# rk86-kbd.net
KiCad netlist of a schematic drawn in EAGLE
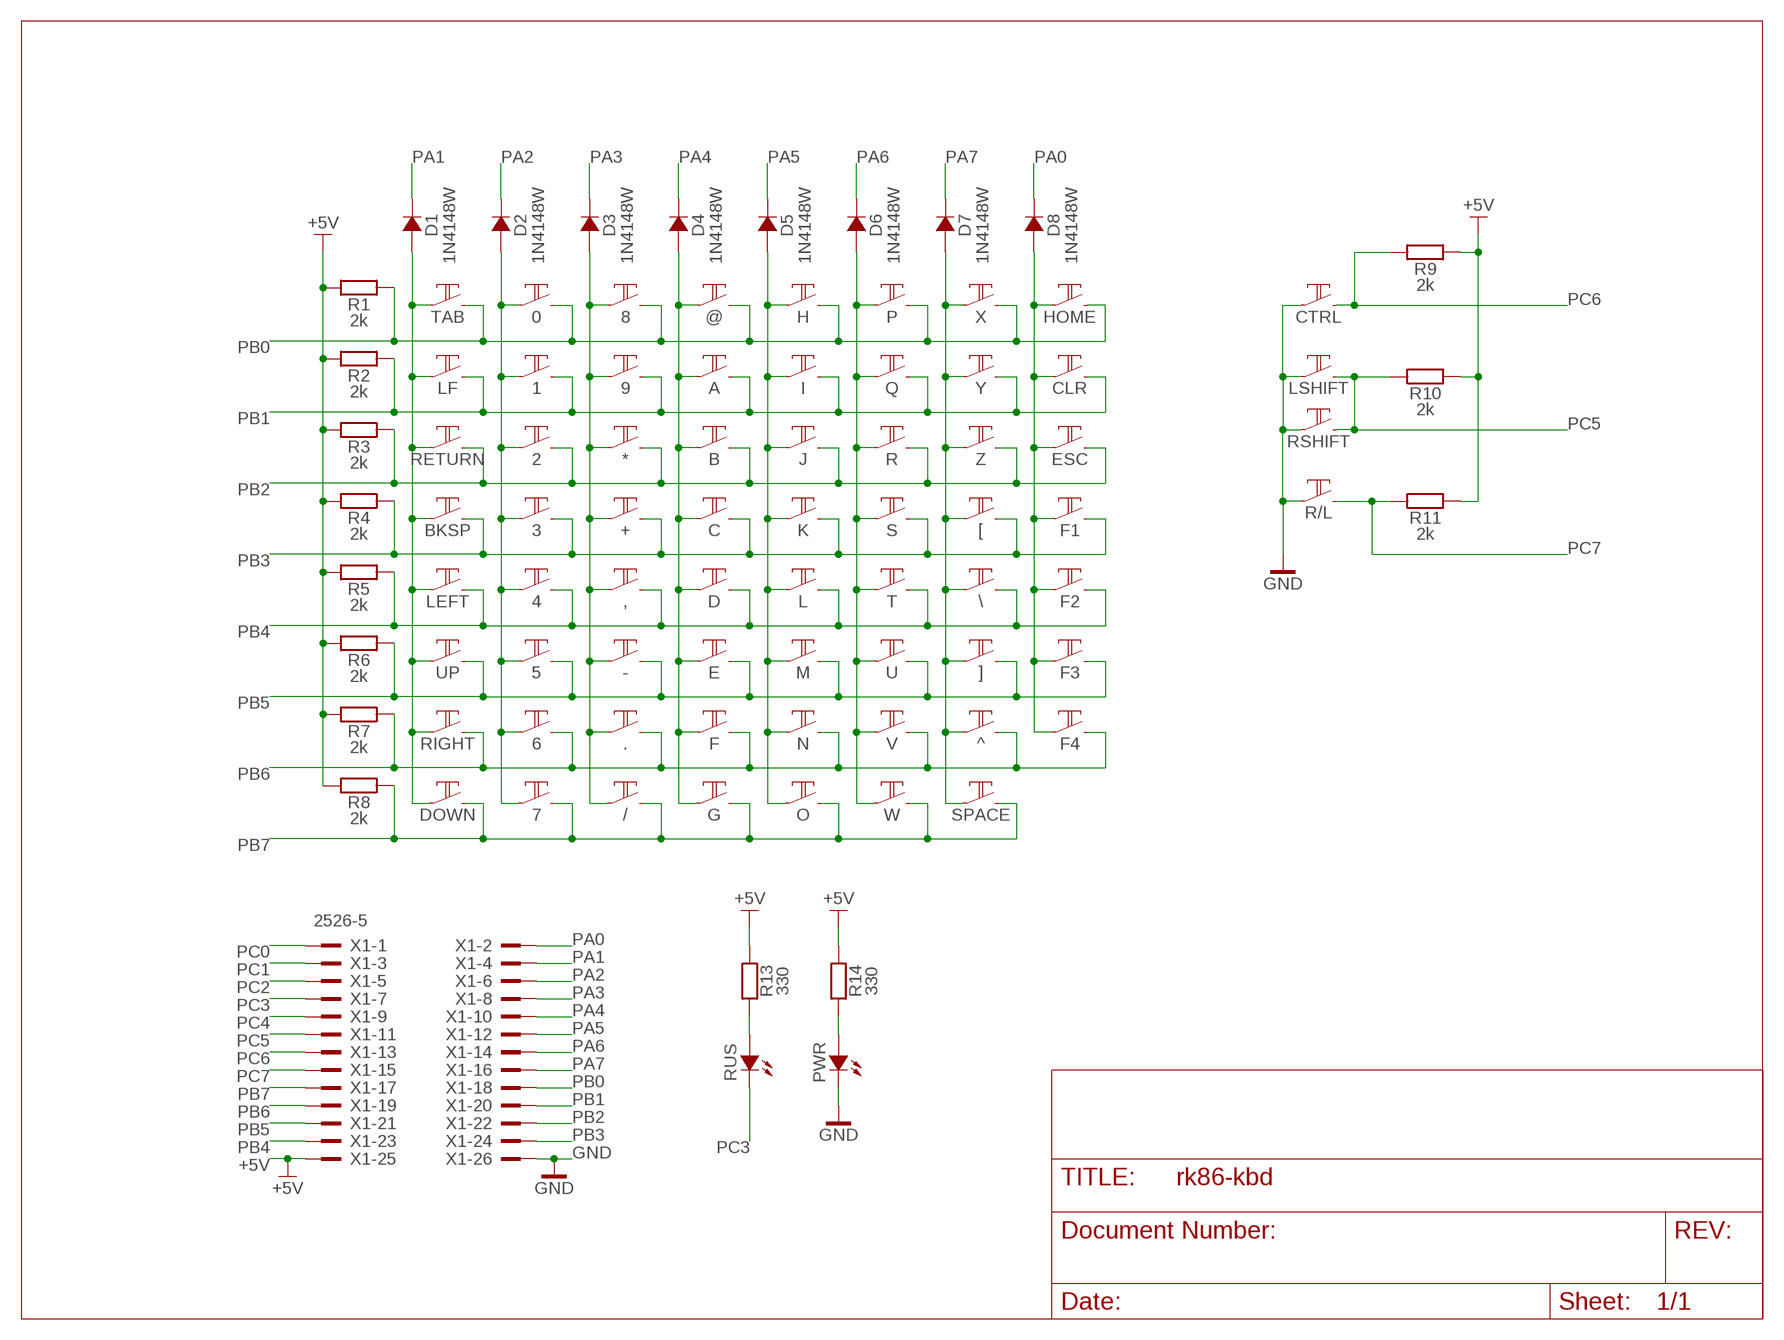
[diagram p0: schematic, sheet 1]

(export (version "E")
  (design (tool "Eeschema 10.0.6"))
  (components
    (comp (ref "*")
      (value "TACT6S-15")
      (footprint "eagle-import:TACT_6X6_SMT_15")
      (libsource (lib "eagle-import") (part "TACT6S-15"))
    )
    (comp (ref "+")
      (value "TACT6S-15")
      (footprint "eagle-import:TACT_6X6_SMT_15")
      (libsource (lib "eagle-import") (part "TACT6S-15"))
    )
    (comp (ref ",")
      (value "TACT6S-15")
      (footprint "eagle-import:TACT_6X6_SMT_15")
      (libsource (lib "eagle-import") (part "TACT6S-15"))
    )
    (comp (ref "-")
      (value "TACT6S-15")
      (footprint "eagle-import:TACT_6X6_SMT_15")
      (libsource (lib "eagle-import") (part "TACT6S-15"))
    )
    (comp (ref ".")
      (value "TACT6S-15")
      (footprint "eagle-import:TACT_6X6_SMT_15")
      (libsource (lib "eagle-import") (part "TACT6S-15"))
    )
    (comp (ref "/")
      (value "TACT6S-15")
      (footprint "eagle-import:TACT_6X6_SMT_15")
      (libsource (lib "eagle-import") (part "TACT6S-15"))
    )
    (comp (ref "0")
      (value "TACT6S-15")
      (footprint "eagle-import:TACT_6X6_SMT_15")
      (libsource (lib "eagle-import") (part "TACT6S-15"))
    )
    (comp (ref "1")
      (value "TACT6S-15")
      (footprint "eagle-import:TACT_6X6_SMT_15")
      (libsource (lib "eagle-import") (part "TACT6S-15"))
    )
    (comp (ref "2")
      (value "TACT6S-15")
      (footprint "eagle-import:TACT_6X6_SMT_15")
      (libsource (lib "eagle-import") (part "TACT6S-15"))
    )
    (comp (ref "3")
      (value "TACT6S-15")
      (footprint "eagle-import:TACT_6X6_SMT_15")
      (libsource (lib "eagle-import") (part "TACT6S-15"))
    )
    (comp (ref "4")
      (value "TACT6S-15")
      (footprint "eagle-import:TACT_6X6_SMT_15")
      (libsource (lib "eagle-import") (part "TACT6S-15"))
    )
    (comp (ref "5")
      (value "TACT6S-15")
      (footprint "eagle-import:TACT_6X6_SMT_15")
      (libsource (lib "eagle-import") (part "TACT6S-15"))
    )
    (comp (ref "6")
      (value "TACT6S-15")
      (footprint "eagle-import:TACT_6X6_SMT_15")
      (libsource (lib "eagle-import") (part "TACT6S-15"))
    )
    (comp (ref "7")
      (value "TACT6S-15")
      (footprint "eagle-import:TACT_6X6_SMT_15")
      (libsource (lib "eagle-import") (part "TACT6S-15"))
    )
    (comp (ref "8")
      (value "TACT6S-15")
      (footprint "eagle-import:TACT_6X6_SMT_15")
      (libsource (lib "eagle-import") (part "TACT6S-15"))
    )
    (comp (ref "9")
      (value "TACT6S-15")
      (footprint "eagle-import:TACT_6X6_SMT_15")
      (libsource (lib "eagle-import") (part "TACT6S-15"))
    )
    (comp (ref "@")
      (value "TACT6S-15")
      (footprint "eagle-import:TACT_6X6_SMT_15")
      (libsource (lib "eagle-import") (part "TACT6S-15"))
    )
    (comp (ref "A")
      (value "TACT6S-15")
      (footprint "eagle-import:TACT_6X6_SMT_15")
      (libsource (lib "eagle-import") (part "TACT6S-15"))
    )
    (comp (ref "B")
      (value "TACT6S-15")
      (footprint "eagle-import:TACT_6X6_SMT_15")
      (libsource (lib "eagle-import") (part "TACT6S-15"))
    )
    (comp (ref "BKSP")
      (value "TACT6S-15")
      (footprint "eagle-import:TACT_6X6_SMT_15")
      (libsource (lib "eagle-import") (part "TACT6S-15"))
    )
    (comp (ref "C")
      (value "TACT6S-15")
      (footprint "eagle-import:TACT_6X6_SMT_15")
      (libsource (lib "eagle-import") (part "TACT6S-15"))
    )
    (comp (ref "CLR")
      (value "TACT6S-15")
      (footprint "eagle-import:TACT_6X6_SMT_15")
      (libsource (lib "eagle-import") (part "TACT6S-15"))
    )
    (comp (ref "CTRL")
      (value "TACT6S-15")
      (footprint "eagle-import:TACT_6X6_SMT_15")
      (libsource (lib "eagle-import") (part "TACT6S-15"))
    )
    (comp (ref "D")
      (value "TACT6S-15")
      (footprint "eagle-import:TACT_6X6_SMT_15")
      (libsource (lib "eagle-import") (part "TACT6S-15"))
    )
    (comp (ref "D1")
      (value "1N4148W")
      (footprint "eagle-import:SOD123")
      (libsource (lib "eagle-import") (part "1N4148W"))
    )
    (comp (ref "D2")
      (value "1N4148W")
      (footprint "eagle-import:SOD123")
      (libsource (lib "eagle-import") (part "1N4148W"))
    )
    (comp (ref "D3")
      (value "1N4148W")
      (footprint "eagle-import:SOD123")
      (libsource (lib "eagle-import") (part "1N4148W"))
    )
    (comp (ref "D4")
      (value "1N4148W")
      (footprint "eagle-import:SOD123")
      (libsource (lib "eagle-import") (part "1N4148W"))
    )
    (comp (ref "D5")
      (value "1N4148W")
      (footprint "eagle-import:SOD123")
      (libsource (lib "eagle-import") (part "1N4148W"))
    )
    (comp (ref "D6")
      (value "1N4148W")
      (footprint "eagle-import:SOD123")
      (libsource (lib "eagle-import") (part "1N4148W"))
    )
    (comp (ref "D7")
      (value "1N4148W")
      (footprint "eagle-import:SOD123")
      (libsource (lib "eagle-import") (part "1N4148W"))
    )
    (comp (ref "D8")
      (value "1N4148W")
      (footprint "eagle-import:SOD123")
      (libsource (lib "eagle-import") (part "1N4148W"))
    )
    (comp (ref "DOWN")
      (value "TACT6S-15")
      (footprint "eagle-import:TACT_6X6_SMT_15")
      (libsource (lib "eagle-import") (part "TACT6S-15"))
    )
    (comp (ref "E")
      (value "TACT6S-15")
      (footprint "eagle-import:TACT_6X6_SMT_15")
      (libsource (lib "eagle-import") (part "TACT6S-15"))
    )
    (comp (ref "ESC")
      (value "TACT6S-15")
      (footprint "eagle-import:TACT_6X6_SMT_15")
      (libsource (lib "eagle-import") (part "TACT6S-15"))
    )
    (comp (ref "F")
      (value "TACT6S-15")
      (footprint "eagle-import:TACT_6X6_SMT_15")
      (libsource (lib "eagle-import") (part "TACT6S-15"))
    )
    (comp (ref "F1")
      (value "TACT6S-15")
      (footprint "eagle-import:TACT_6X6_SMT_15")
      (libsource (lib "eagle-import") (part "TACT6S-15"))
    )
    (comp (ref "F2")
      (value "TACT6S-15")
      (footprint "eagle-import:TACT_6X6_SMT_15")
      (libsource (lib "eagle-import") (part "TACT6S-15"))
    )
    (comp (ref "F3")
      (value "TACT6S-15")
      (footprint "eagle-import:TACT_6X6_SMT_15")
      (libsource (lib "eagle-import") (part "TACT6S-15"))
    )
    (comp (ref "F4")
      (value "TACT6S-15")
      (footprint "eagle-import:TACT_6X6_SMT_15")
      (libsource (lib "eagle-import") (part "TACT6S-15"))
    )
    (comp (ref "G")
      (value "TACT6S-15")
      (footprint "eagle-import:TACT_6X6_SMT_15")
      (libsource (lib "eagle-import") (part "TACT6S-15"))
    )
    (comp (ref "H")
      (value "TACT6S-15")
      (footprint "eagle-import:TACT_6X6_SMT_15")
      (libsource (lib "eagle-import") (part "TACT6S-15"))
    )
    (comp (ref "HOME")
      (value "TACT6S-15")
      (footprint "eagle-import:TACT_6X6_SMT_15")
      (libsource (lib "eagle-import") (part "TACT6S-15"))
    )
    (comp (ref "I")
      (value "TACT6S-15")
      (footprint "eagle-import:TACT_6X6_SMT_15")
      (libsource (lib "eagle-import") (part "TACT6S-15"))
    )
    (comp (ref "J")
      (value "TACT6S-15")
      (footprint "eagle-import:TACT_6X6_SMT_15")
      (libsource (lib "eagle-import") (part "TACT6S-15"))
    )
    (comp (ref "K")
      (value "TACT6S-15")
      (footprint "eagle-import:TACT_6X6_SMT_15")
      (libsource (lib "eagle-import") (part "TACT6S-15"))
    )
    (comp (ref "L")
      (value "TACT6S-15")
      (footprint "eagle-import:TACT_6X6_SMT_15")
      (libsource (lib "eagle-import") (part "TACT6S-15"))
    )
    (comp (ref "LEFT")
      (value "TACT6S-15")
      (footprint "eagle-import:TACT_6X6_SMT_15")
      (libsource (lib "eagle-import") (part "TACT6S-15"))
    )
    (comp (ref "LF")
      (value "TACT6S-15")
      (footprint "eagle-import:TACT_6X6_SMT_15")
      (libsource (lib "eagle-import") (part "TACT6S-15"))
    )
    (comp (ref "LSHIFT")
      (value "TACT6S-15")
      (footprint "eagle-import:TACT_6X6_SMT_15")
      (libsource (lib "eagle-import") (part "TACT6S-15"))
    )
    (comp (ref "M")
      (value "TACT6S-15")
      (footprint "eagle-import:TACT_6X6_SMT_15")
      (libsource (lib "eagle-import") (part "TACT6S-15"))
    )
    (comp (ref "N")
      (value "TACT6S-15")
      (footprint "eagle-import:TACT_6X6_SMT_15")
      (libsource (lib "eagle-import") (part "TACT6S-15"))
    )
    (comp (ref "O")
      (value "TACT6S-15")
      (footprint "eagle-import:TACT_6X6_SMT_15")
      (libsource (lib "eagle-import") (part "TACT6S-15"))
    )
    (comp (ref "P")
      (value "TACT6S-15")
      (footprint "eagle-import:TACT_6X6_SMT_15")
      (libsource (lib "eagle-import") (part "TACT6S-15"))
    )
    (comp (ref "PWR")
      (value "LED0805")
      (footprint "eagle-import:0805POL")
      (libsource (lib "eagle-import") (part "LED0805"))
    )
    (comp (ref "Q")
      (value "TACT6S-15")
      (footprint "eagle-import:TACT_6X6_SMT_15")
      (libsource (lib "eagle-import") (part "TACT6S-15"))
    )
    (comp (ref "R")
      (value "TACT6S-15")
      (footprint "eagle-import:TACT_6X6_SMT_15")
      (libsource (lib "eagle-import") (part "TACT6S-15"))
    )
    (comp (ref "R/L")
      (value "TACT6S-15")
      (footprint "eagle-import:TACT_6X6_SMT_15")
      (libsource (lib "eagle-import") (part "TACT6S-15"))
    )
    (comp (ref "R1")
      (value "2k")
      (footprint "eagle-import:0805")
      (libsource (lib "eagle-import") (part "RESISTOR0805"))
    )
    (comp (ref "R2")
      (value "2k")
      (footprint "eagle-import:0805")
      (libsource (lib "eagle-import") (part "RESISTOR0805"))
    )
    (comp (ref "R3")
      (value "2k")
      (footprint "eagle-import:0805")
      (libsource (lib "eagle-import") (part "RESISTOR0805"))
    )
    (comp (ref "R4")
      (value "2k")
      (footprint "eagle-import:0805")
      (libsource (lib "eagle-import") (part "RESISTOR0805"))
    )
    (comp (ref "R5")
      (value "2k")
      (footprint "eagle-import:0805")
      (libsource (lib "eagle-import") (part "RESISTOR0805"))
    )
    (comp (ref "R6")
      (value "2k")
      (footprint "eagle-import:0805")
      (libsource (lib "eagle-import") (part "RESISTOR0805"))
    )
    (comp (ref "R7")
      (value "2k")
      (footprint "eagle-import:0805")
      (libsource (lib "eagle-import") (part "RESISTOR0805"))
    )
    (comp (ref "R8")
      (value "2k")
      (footprint "eagle-import:0805")
      (libsource (lib "eagle-import") (part "RESISTOR0805"))
    )
    (comp (ref "R9")
      (value "2k")
      (footprint "eagle-import:0805")
      (libsource (lib "eagle-import") (part "RESISTOR0805"))
    )
    (comp (ref "R10")
      (value "2k")
      (footprint "eagle-import:0805")
      (libsource (lib "eagle-import") (part "RESISTOR0805"))
    )
    (comp (ref "R11")
      (value "2k")
      (footprint "eagle-import:0805")
      (libsource (lib "eagle-import") (part "RESISTOR0805"))
    )
    (comp (ref "R13")
      (value "330")
      (footprint "eagle-import:0805")
      (libsource (lib "eagle-import") (part "RESISTOR0805"))
    )
    (comp (ref "R14")
      (value "330")
      (footprint "eagle-import:0805")
      (libsource (lib "eagle-import") (part "RESISTOR0805"))
    )
    (comp (ref "RETURN")
      (value "TACT6S-15")
      (footprint "eagle-import:TACT_6X6_SMT_15")
      (libsource (lib "eagle-import") (part "TACT6S-15"))
    )
    (comp (ref "RIGHT")
      (value "TACT6S-15")
      (footprint "eagle-import:TACT_6X6_SMT_15")
      (libsource (lib "eagle-import") (part "TACT6S-15"))
    )
    (comp (ref "RSHIFT")
      (value "TACT6S-15")
      (footprint "eagle-import:TACT_6X6_SMT_15")
      (libsource (lib "eagle-import") (part "TACT6S-15"))
    )
    (comp (ref "RUS")
      (value "LED0805")
      (footprint "eagle-import:0805POL")
      (libsource (lib "eagle-import") (part "LED0805"))
    )
    (comp (ref "S")
      (value "TACT6S-15")
      (footprint "eagle-import:TACT_6X6_SMT_15")
      (libsource (lib "eagle-import") (part "TACT6S-15"))
    )
    (comp (ref "SPACE")
      (value "TACT6S-15")
      (footprint "eagle-import:TACT_6X6_SMT_15")
      (libsource (lib "eagle-import") (part "TACT6S-15"))
    )
    (comp (ref "T")
      (value "TACT6S-15")
      (footprint "eagle-import:TACT_6X6_SMT_15")
      (libsource (lib "eagle-import") (part "TACT6S-15"))
    )
    (comp (ref "TAB")
      (value "TACT6S-15")
      (footprint "eagle-import:TACT_6X6_SMT_15")
      (libsource (lib "eagle-import") (part "TACT6S-15"))
    )
    (comp (ref "U")
      (value "TACT6S-15")
      (footprint "eagle-import:TACT_6X6_SMT_15")
      (libsource (lib "eagle-import") (part "TACT6S-15"))
    )
    (comp (ref "UP")
      (value "TACT6S-15")
      (footprint "eagle-import:TACT_6X6_SMT_15")
      (libsource (lib "eagle-import") (part "TACT6S-15"))
    )
    (comp (ref "V")
      (value "TACT6S-15")
      (footprint "eagle-import:TACT_6X6_SMT_15")
      (libsource (lib "eagle-import") (part "TACT6S-15"))
    )
    (comp (ref "W")
      (value "TACT6S-15")
      (footprint "eagle-import:TACT_6X6_SMT_15")
      (libsource (lib "eagle-import") (part "TACT6S-15"))
    )
    (comp (ref "X")
      (value "TACT6S-15")
      (footprint "eagle-import:TACT_6X6_SMT_15")
      (libsource (lib "eagle-import") (part "TACT6S-15"))
    )
    (comp (ref "X1")
      (value "2526-5")
      (footprint "eagle-import:PAK100_2500-5-26")
      (libsource (lib "eagle-import") (part "2526-5"))
    )
    (comp (ref "Y")
      (value "TACT6S-15")
      (footprint "eagle-import:TACT_6X6_SMT_15")
      (libsource (lib "eagle-import") (part "TACT6S-15"))
    )
    (comp (ref "Z")
      (value "TACT6S-15")
      (footprint "eagle-import:TACT_6X6_SMT_15")
      (libsource (lib "eagle-import") (part "TACT6S-15"))
    )
    (comp (ref "[")
      (value "TACT6S-15")
      (footprint "eagle-import:TACT_6X6_SMT_15")
      (libsource (lib "eagle-import") (part "TACT6S-15"))
    )
    (comp (ref "\\\\")
      (value "TACT6S-15")
      (footprint "eagle-import:TACT_6X6_SMT_15")
      (libsource (lib "eagle-import") (part "TACT6S-15"))
    )
    (comp (ref "]")
      (value "TACT6S-15")
      (footprint "eagle-import:TACT_6X6_SMT_15")
      (libsource (lib "eagle-import") (part "TACT6S-15"))
    )
    (comp (ref "^")
      (value "TACT6S-15")
      (footprint "eagle-import:TACT_6X6_SMT_15")
      (libsource (lib "eagle-import") (part "TACT6S-15"))
    )
  )
  (nets
    (net (code "1") (name "+5V") (class "Default")
      (node (ref "R1") (pin "1") (pinfunction "P$1_1") (pintype "passive"))
      (node (ref "R10") (pin "2") (pinfunction "P$2_2") (pintype "passive"))
      (node (ref "R11") (pin "2") (pinfunction "P$2_2") (pintype "passive"))
      (node (ref "R13") (pin "2") (pinfunction "P$2_2") (pintype "passive"))
      (node (ref "R14") (pin "2") (pinfunction "P$2_2") (pintype "passive"))
      (node (ref "R2") (pin "1") (pinfunction "P$1_1") (pintype "passive"))
      (node (ref "R3") (pin "1") (pinfunction "P$1_1") (pintype "passive"))
      (node (ref "R4") (pin "1") (pinfunction "P$1_1") (pintype "passive"))
      (node (ref "R5") (pin "1") (pinfunction "P$1_1") (pintype "passive"))
      (node (ref "R6") (pin "1") (pinfunction "P$1_1") (pintype "passive"))
      (node (ref "R7") (pin "1") (pinfunction "P$1_1") (pintype "passive"))
      (node (ref "R8") (pin "1") (pinfunction "P$1_1") (pintype "passive"))
      (node (ref "R9") (pin "2") (pinfunction "P$2_2") (pintype "passive"))
      (node (ref "X1") (pin "25") (pinfunction "KL_25") (pintype "passive"))
    )
    (net (code "2") (name "/PA0") (class "Default")
      (node (ref "D8") (pin "K") (pinfunction "K_K") (pintype "passive"))
      (node (ref "X1") (pin "2") (pinfunction "KL_2") (pintype "passive"))
    )
    (net (code "3") (name "/PA1") (class "Default")
      (node (ref "D1") (pin "K") (pinfunction "K_K") (pintype "passive"))
      (node (ref "X1") (pin "4") (pinfunction "KL_4") (pintype "passive"))
    )
    (net (code "4") (name "/PA2") (class "Default")
      (node (ref "D2") (pin "K") (pinfunction "K_K") (pintype "passive"))
      (node (ref "X1") (pin "6") (pinfunction "KL_6") (pintype "passive"))
    )
    (net (code "5") (name "/PA3") (class "Default")
      (node (ref "D3") (pin "K") (pinfunction "K_K") (pintype "passive"))
      (node (ref "X1") (pin "8") (pinfunction "KL_8") (pintype "passive"))
    )
    (net (code "6") (name "/PA4") (class "Default")
      (node (ref "D4") (pin "K") (pinfunction "K_K") (pintype "passive"))
      (node (ref "X1") (pin "10") (pinfunction "KL_10") (pintype "passive"))
    )
    (net (code "7") (name "/PA5") (class "Default")
      (node (ref "D5") (pin "K") (pinfunction "K_K") (pintype "passive"))
      (node (ref "X1") (pin "12") (pinfunction "KL_12") (pintype "passive"))
    )
    (net (code "8") (name "/PA6") (class "Default")
      (node (ref "D6") (pin "K") (pinfunction "K_K") (pintype "passive"))
      (node (ref "X1") (pin "14") (pinfunction "KL_14") (pintype "passive"))
    )
    (net (code "9") (name "/PA7") (class "Default")
      (node (ref "D7") (pin "K") (pinfunction "K_K") (pintype "passive"))
      (node (ref "X1") (pin "16") (pinfunction "KL_16") (pintype "passive"))
    )
    (net (code "10") (name "/PB0") (class "Default")
      (node (ref "0") (pin "3") (pinfunction "NO_3") (pintype "passive"))
      (node (ref "0") (pin "4") (pinfunction "NO_4") (pintype "passive"))
      (node (ref "8") (pin "3") (pinfunction "NO_3") (pintype "passive"))
      (node (ref "8") (pin "4") (pinfunction "NO_4") (pintype "passive"))
      (node (ref "@") (pin "3") (pinfunction "NO_3") (pintype "passive"))
      (node (ref "@") (pin "4") (pinfunction "NO_4") (pintype "passive"))
      (node (ref "H") (pin "3") (pinfunction "NO_3") (pintype "passive"))
      (node (ref "H") (pin "4") (pinfunction "NO_4") (pintype "passive"))
      (node (ref "HOME") (pin "3") (pinfunction "NO_3") (pintype "passive"))
      (node (ref "HOME") (pin "4") (pinfunction "NO_4") (pintype "passive"))
      (node (ref "P") (pin "3") (pinfunction "NO_3") (pintype "passive"))
      (node (ref "P") (pin "4") (pinfunction "NO_4") (pintype "passive"))
      (node (ref "R1") (pin "2") (pinfunction "P$2_2") (pintype "passive"))
      (node (ref "TAB") (pin "3") (pinfunction "NO_3") (pintype "passive"))
      (node (ref "TAB") (pin "4") (pinfunction "NO_4") (pintype "passive"))
      (node (ref "X") (pin "3") (pinfunction "NO_3") (pintype "passive"))
      (node (ref "X") (pin "4") (pinfunction "NO_4") (pintype "passive"))
      (node (ref "X1") (pin "18") (pinfunction "KL_18") (pintype "passive"))
    )
    (net (code "11") (name "/PB1") (class "Default")
      (node (ref "1") (pin "3") (pinfunction "NO_3") (pintype "passive"))
      (node (ref "1") (pin "4") (pinfunction "NO_4") (pintype "passive"))
      (node (ref "9") (pin "3") (pinfunction "NO_3") (pintype "passive"))
      (node (ref "9") (pin "4") (pinfunction "NO_4") (pintype "passive"))
      (node (ref "A") (pin "3") (pinfunction "NO_3") (pintype "passive"))
      (node (ref "A") (pin "4") (pinfunction "NO_4") (pintype "passive"))
      (node (ref "CLR") (pin "3") (pinfunction "NO_3") (pintype "passive"))
      (node (ref "CLR") (pin "4") (pinfunction "NO_4") (pintype "passive"))
      (node (ref "I") (pin "3") (pinfunction "NO_3") (pintype "passive"))
      (node (ref "I") (pin "4") (pinfunction "NO_4") (pintype "passive"))
      (node (ref "LF") (pin "3") (pinfunction "NO_3") (pintype "passive"))
      (node (ref "LF") (pin "4") (pinfunction "NO_4") (pintype "passive"))
      (node (ref "Q") (pin "3") (pinfunction "NO_3") (pintype "passive"))
      (node (ref "Q") (pin "4") (pinfunction "NO_4") (pintype "passive"))
      (node (ref "R2") (pin "2") (pinfunction "P$2_2") (pintype "passive"))
      (node (ref "X1") (pin "20") (pinfunction "KL_20") (pintype "passive"))
      (node (ref "Y") (pin "3") (pinfunction "NO_3") (pintype "passive"))
      (node (ref "Y") (pin "4") (pinfunction "NO_4") (pintype "passive"))
    )
    (net (code "12") (name "/PB2") (class "Default")
      (node (ref "*") (pin "3") (pinfunction "NO_3") (pintype "passive"))
      (node (ref "*") (pin "4") (pinfunction "NO_4") (pintype "passive"))
      (node (ref "2") (pin "3") (pinfunction "NO_3") (pintype "passive"))
      (node (ref "2") (pin "4") (pinfunction "NO_4") (pintype "passive"))
      (node (ref "B") (pin "3") (pinfunction "NO_3") (pintype "passive"))
      (node (ref "B") (pin "4") (pinfunction "NO_4") (pintype "passive"))
      (node (ref "ESC") (pin "3") (pinfunction "NO_3") (pintype "passive"))
      (node (ref "ESC") (pin "4") (pinfunction "NO_4") (pintype "passive"))
      (node (ref "J") (pin "3") (pinfunction "NO_3") (pintype "passive"))
      (node (ref "J") (pin "4") (pinfunction "NO_4") (pintype "passive"))
      (node (ref "R") (pin "3") (pinfunction "NO_3") (pintype "passive"))
      (node (ref "R") (pin "4") (pinfunction "NO_4") (pintype "passive"))
      (node (ref "R3") (pin "2") (pinfunction "P$2_2") (pintype "passive"))
      (node (ref "RETURN") (pin "3") (pinfunction "NO_3") (pintype "passive"))
      (node (ref "RETURN") (pin "4") (pinfunction "NO_4") (pintype "passive"))
      (node (ref "X1") (pin "22") (pinfunction "KL_22") (pintype "passive"))
      (node (ref "Z") (pin "3") (pinfunction "NO_3") (pintype "passive"))
      (node (ref "Z") (pin "4") (pinfunction "NO_4") (pintype "passive"))
    )
    (net (code "13") (name "/PB3") (class "Default")
      (node (ref "+") (pin "3") (pinfunction "NO_3") (pintype "passive"))
      (node (ref "+") (pin "4") (pinfunction "NO_4") (pintype "passive"))
      (node (ref "3") (pin "3") (pinfunction "NO_3") (pintype "passive"))
      (node (ref "3") (pin "4") (pinfunction "NO_4") (pintype "passive"))
      (node (ref "BKSP") (pin "3") (pinfunction "NO_3") (pintype "passive"))
      (node (ref "BKSP") (pin "4") (pinfunction "NO_4") (pintype "passive"))
      (node (ref "C") (pin "3") (pinfunction "NO_3") (pintype "passive"))
      (node (ref "C") (pin "4") (pinfunction "NO_4") (pintype "passive"))
      (node (ref "F1") (pin "3") (pinfunction "NO_3") (pintype "passive"))
      (node (ref "F1") (pin "4") (pinfunction "NO_4") (pintype "passive"))
      (node (ref "K") (pin "3") (pinfunction "NO_3") (pintype "passive"))
      (node (ref "K") (pin "4") (pinfunction "NO_4") (pintype "passive"))
      (node (ref "R4") (pin "2") (pinfunction "P$2_2") (pintype "passive"))
      (node (ref "S") (pin "3") (pinfunction "NO_3") (pintype "passive"))
      (node (ref "S") (pin "4") (pinfunction "NO_4") (pintype "passive"))
      (node (ref "X1") (pin "24") (pinfunction "KL_24") (pintype "passive"))
      (node (ref "[") (pin "3") (pinfunction "NO_3") (pintype "passive"))
      (node (ref "[") (pin "4") (pinfunction "NO_4") (pintype "passive"))
    )
    (net (code "14") (name "/PB4") (class "Default")
      (node (ref ",") (pin "3") (pinfunction "NO_3") (pintype "passive"))
      (node (ref ",") (pin "4") (pinfunction "NO_4") (pintype "passive"))
      (node (ref "4") (pin "3") (pinfunction "NO_3") (pintype "passive"))
      (node (ref "4") (pin "4") (pinfunction "NO_4") (pintype "passive"))
      (node (ref "D") (pin "3") (pinfunction "NO_3") (pintype "passive"))
      (node (ref "D") (pin "4") (pinfunction "NO_4") (pintype "passive"))
      (node (ref "F2") (pin "3") (pinfunction "NO_3") (pintype "passive"))
      (node (ref "F2") (pin "4") (pinfunction "NO_4") (pintype "passive"))
      (node (ref "L") (pin "3") (pinfunction "NO_3") (pintype "passive"))
      (node (ref "L") (pin "4") (pinfunction "NO_4") (pintype "passive"))
      (node (ref "LEFT") (pin "3") (pinfunction "NO_3") (pintype "passive"))
      (node (ref "LEFT") (pin "4") (pinfunction "NO_4") (pintype "passive"))
      (node (ref "R5") (pin "2") (pinfunction "P$2_2") (pintype "passive"))
      (node (ref "T") (pin "3") (pinfunction "NO_3") (pintype "passive"))
      (node (ref "T") (pin "4") (pinfunction "NO_4") (pintype "passive"))
      (node (ref "X1") (pin "23") (pinfunction "KL_23") (pintype "passive"))
      (node (ref "\\\\") (pin "3") (pinfunction "NO_3") (pintype "passive"))
      (node (ref "\\\\") (pin "4") (pinfunction "NO_4") (pintype "passive"))
    )
    (net (code "15") (name "/PB5") (class "Default")
      (node (ref "-") (pin "3") (pinfunction "NO_3") (pintype "passive"))
      (node (ref "-") (pin "4") (pinfunction "NO_4") (pintype "passive"))
      (node (ref "5") (pin "3") (pinfunction "NO_3") (pintype "passive"))
      (node (ref "5") (pin "4") (pinfunction "NO_4") (pintype "passive"))
      (node (ref "E") (pin "3") (pinfunction "NO_3") (pintype "passive"))
      (node (ref "E") (pin "4") (pinfunction "NO_4") (pintype "passive"))
      (node (ref "F3") (pin "3") (pinfunction "NO_3") (pintype "passive"))
      (node (ref "F3") (pin "4") (pinfunction "NO_4") (pintype "passive"))
      (node (ref "M") (pin "3") (pinfunction "NO_3") (pintype "passive"))
      (node (ref "M") (pin "4") (pinfunction "NO_4") (pintype "passive"))
      (node (ref "R6") (pin "2") (pinfunction "P$2_2") (pintype "passive"))
      (node (ref "U") (pin "3") (pinfunction "NO_3") (pintype "passive"))
      (node (ref "U") (pin "4") (pinfunction "NO_4") (pintype "passive"))
      (node (ref "UP") (pin "3") (pinfunction "NO_3") (pintype "passive"))
      (node (ref "UP") (pin "4") (pinfunction "NO_4") (pintype "passive"))
      (node (ref "X1") (pin "21") (pinfunction "KL_21") (pintype "passive"))
      (node (ref "]") (pin "3") (pinfunction "NO_3") (pintype "passive"))
      (node (ref "]") (pin "4") (pinfunction "NO_4") (pintype "passive"))
    )
    (net (code "16") (name "/PB6") (class "Default")
      (node (ref ".") (pin "3") (pinfunction "NO_3") (pintype "passive"))
      (node (ref ".") (pin "4") (pinfunction "NO_4") (pintype "passive"))
      (node (ref "6") (pin "3") (pinfunction "NO_3") (pintype "passive"))
      (node (ref "6") (pin "4") (pinfunction "NO_4") (pintype "passive"))
      (node (ref "F") (pin "3") (pinfunction "NO_3") (pintype "passive"))
      (node (ref "F") (pin "4") (pinfunction "NO_4") (pintype "passive"))
      (node (ref "F4") (pin "3") (pinfunction "NO_3") (pintype "passive"))
      (node (ref "F4") (pin "4") (pinfunction "NO_4") (pintype "passive"))
      (node (ref "N") (pin "3") (pinfunction "NO_3") (pintype "passive"))
      (node (ref "N") (pin "4") (pinfunction "NO_4") (pintype "passive"))
      (node (ref "R7") (pin "2") (pinfunction "P$2_2") (pintype "passive"))
      (node (ref "RIGHT") (pin "3") (pinfunction "NO_3") (pintype "passive"))
      (node (ref "RIGHT") (pin "4") (pinfunction "NO_4") (pintype "passive"))
      (node (ref "V") (pin "3") (pinfunction "NO_3") (pintype "passive"))
      (node (ref "V") (pin "4") (pinfunction "NO_4") (pintype "passive"))
      (node (ref "X1") (pin "19") (pinfunction "KL_19") (pintype "passive"))
      (node (ref "^") (pin "3") (pinfunction "NO_3") (pintype "passive"))
      (node (ref "^") (pin "4") (pinfunction "NO_4") (pintype "passive"))
    )
    (net (code "17") (name "/PB7") (class "Default")
      (node (ref "/") (pin "3") (pinfunction "NO_3") (pintype "passive"))
      (node (ref "/") (pin "4") (pinfunction "NO_4") (pintype "passive"))
      (node (ref "7") (pin "3") (pinfunction "NO_3") (pintype "passive"))
      (node (ref "7") (pin "4") (pinfunction "NO_4") (pintype "passive"))
      (node (ref "DOWN") (pin "3") (pinfunction "NO_3") (pintype "passive"))
      (node (ref "DOWN") (pin "4") (pinfunction "NO_4") (pintype "passive"))
      (node (ref "G") (pin "3") (pinfunction "NO_3") (pintype "passive"))
      (node (ref "G") (pin "4") (pinfunction "NO_4") (pintype "passive"))
      (node (ref "O") (pin "3") (pinfunction "NO_3") (pintype "passive"))
      (node (ref "O") (pin "4") (pinfunction "NO_4") (pintype "passive"))
      (node (ref "R8") (pin "2") (pinfunction "P$2_2") (pintype "passive"))
      (node (ref "SPACE") (pin "3") (pinfunction "NO_3") (pintype "passive"))
      (node (ref "SPACE") (pin "4") (pinfunction "NO_4") (pintype "passive"))
      (node (ref "W") (pin "3") (pinfunction "NO_3") (pintype "passive"))
      (node (ref "W") (pin "4") (pinfunction "NO_4") (pintype "passive"))
      (node (ref "X1") (pin "17") (pinfunction "KL_17") (pintype "passive"))
    )
    (net (code "18") (name "/PC0") (class "Default")
      (node (ref "X1") (pin "1") (pinfunction "KL_1") (pintype "passive"))
    )
    (net (code "19") (name "/PC1") (class "Default")
      (node (ref "X1") (pin "3") (pinfunction "KL_3") (pintype "passive"))
    )
    (net (code "20") (name "/PC2") (class "Default")
      (node (ref "X1") (pin "5") (pinfunction "KL_5") (pintype "passive"))
    )
    (net (code "21") (name "/PC3") (class "Default")
      (node (ref "RUS") (pin "K") (pinfunction "K_K") (pintype "passive"))
      (node (ref "X1") (pin "7") (pinfunction "KL_7") (pintype "passive"))
    )
    (net (code "22") (name "/PC4") (class "Default")
      (node (ref "X1") (pin "9") (pinfunction "KL_9") (pintype "passive"))
    )
    (net (code "23") (name "/PC5") (class "Default")
      (node (ref "LSHIFT") (pin "3") (pinfunction "NO_3") (pintype "passive"))
      (node (ref "LSHIFT") (pin "4") (pinfunction "NO_4") (pintype "passive"))
      (node (ref "R10") (pin "1") (pinfunction "P$1_1") (pintype "passive"))
      (node (ref "RSHIFT") (pin "3") (pinfunction "NO_3") (pintype "passive"))
      (node (ref "RSHIFT") (pin "4") (pinfunction "NO_4") (pintype "passive"))
      (node (ref "X1") (pin "11") (pinfunction "KL_11") (pintype "passive"))
    )
    (net (code "24") (name "/PC6") (class "Default")
      (node (ref "CTRL") (pin "3") (pinfunction "NO_3") (pintype "passive"))
      (node (ref "CTRL") (pin "4") (pinfunction "NO_4") (pintype "passive"))
      (node (ref "R9") (pin "1") (pinfunction "P$1_1") (pintype "passive"))
      (node (ref "X1") (pin "13") (pinfunction "KL_13") (pintype "passive"))
    )
    (net (code "25") (name "/PC7") (class "Default")
      (node (ref "R/L") (pin "3") (pinfunction "NO_3") (pintype "passive"))
      (node (ref "R/L") (pin "4") (pinfunction "NO_4") (pintype "passive"))
      (node (ref "R11") (pin "1") (pinfunction "P$1_1") (pintype "passive"))
      (node (ref "X1") (pin "15") (pinfunction "KL_15") (pintype "passive"))
    )
    (net (code "26") (name "GND") (class "Default")
      (node (ref "CTRL") (pin "1") (pinfunction "C_1") (pintype "passive"))
      (node (ref "CTRL") (pin "2") (pinfunction "C_2") (pintype "passive"))
      (node (ref "LSHIFT") (pin "1") (pinfunction "C_1") (pintype "passive"))
      (node (ref "LSHIFT") (pin "2") (pinfunction "C_2") (pintype "passive"))
      (node (ref "PWR") (pin "K") (pinfunction "K_K") (pintype "passive"))
      (node (ref "R/L") (pin "1") (pinfunction "C_1") (pintype "passive"))
      (node (ref "R/L") (pin "2") (pinfunction "C_2") (pintype "passive"))
      (node (ref "RSHIFT") (pin "1") (pinfunction "C_1") (pintype "passive"))
      (node (ref "RSHIFT") (pin "2") (pinfunction "C_2") (pintype "passive"))
      (node (ref "X1") (pin "26") (pinfunction "KL_26") (pintype "passive"))
    )
    (net (code "27") (name "Net-(*-C-Pad1)") (class "Default")
      (node (ref "*") (pin "1") (pinfunction "C_1") (pintype "passive"))
      (node (ref "*") (pin "2") (pinfunction "C_2") (pintype "passive"))
      (node (ref "+") (pin "1") (pinfunction "C_1") (pintype "passive"))
      (node (ref "+") (pin "2") (pinfunction "C_2") (pintype "passive"))
      (node (ref ",") (pin "1") (pinfunction "C_1") (pintype "passive"))
      (node (ref ",") (pin "2") (pinfunction "C_2") (pintype "passive"))
      (node (ref "-") (pin "1") (pinfunction "C_1") (pintype "passive"))
      (node (ref "-") (pin "2") (pinfunction "C_2") (pintype "passive"))
      (node (ref ".") (pin "1") (pinfunction "C_1") (pintype "passive"))
      (node (ref ".") (pin "2") (pinfunction "C_2") (pintype "passive"))
      (node (ref "/") (pin "1") (pinfunction "C_1") (pintype "passive"))
      (node (ref "/") (pin "2") (pinfunction "C_2") (pintype "passive"))
      (node (ref "8") (pin "1") (pinfunction "C_1") (pintype "passive"))
      (node (ref "8") (pin "2") (pinfunction "C_2") (pintype "passive"))
      (node (ref "9") (pin "1") (pinfunction "C_1") (pintype "passive"))
      (node (ref "9") (pin "2") (pinfunction "C_2") (pintype "passive"))
      (node (ref "D3") (pin "A") (pinfunction "A_A") (pintype "passive"))
    )
    (net (code "28") (name "Net-(0-C-Pad1)") (class "Default")
      (node (ref "0") (pin "1") (pinfunction "C_1") (pintype "passive"))
      (node (ref "0") (pin "2") (pinfunction "C_2") (pintype "passive"))
      (node (ref "1") (pin "1") (pinfunction "C_1") (pintype "passive"))
      (node (ref "1") (pin "2") (pinfunction "C_2") (pintype "passive"))
      (node (ref "2") (pin "1") (pinfunction "C_1") (pintype "passive"))
      (node (ref "2") (pin "2") (pinfunction "C_2") (pintype "passive"))
      (node (ref "3") (pin "1") (pinfunction "C_1") (pintype "passive"))
      (node (ref "3") (pin "2") (pinfunction "C_2") (pintype "passive"))
      (node (ref "4") (pin "1") (pinfunction "C_1") (pintype "passive"))
      (node (ref "4") (pin "2") (pinfunction "C_2") (pintype "passive"))
      (node (ref "5") (pin "1") (pinfunction "C_1") (pintype "passive"))
      (node (ref "5") (pin "2") (pinfunction "C_2") (pintype "passive"))
      (node (ref "6") (pin "1") (pinfunction "C_1") (pintype "passive"))
      (node (ref "6") (pin "2") (pinfunction "C_2") (pintype "passive"))
      (node (ref "7") (pin "1") (pinfunction "C_1") (pintype "passive"))
      (node (ref "7") (pin "2") (pinfunction "C_2") (pintype "passive"))
      (node (ref "D2") (pin "A") (pinfunction "A_A") (pintype "passive"))
    )
    (net (code "29") (name "Net-(@-C-Pad1)") (class "Default")
      (node (ref "@") (pin "1") (pinfunction "C_1") (pintype "passive"))
      (node (ref "@") (pin "2") (pinfunction "C_2") (pintype "passive"))
      (node (ref "A") (pin "1") (pinfunction "C_1") (pintype "passive"))
      (node (ref "A") (pin "2") (pinfunction "C_2") (pintype "passive"))
      (node (ref "B") (pin "1") (pinfunction "C_1") (pintype "passive"))
      (node (ref "B") (pin "2") (pinfunction "C_2") (pintype "passive"))
      (node (ref "C") (pin "1") (pinfunction "C_1") (pintype "passive"))
      (node (ref "C") (pin "2") (pinfunction "C_2") (pintype "passive"))
      (node (ref "D") (pin "1") (pinfunction "C_1") (pintype "passive"))
      (node (ref "D") (pin "2") (pinfunction "C_2") (pintype "passive"))
      (node (ref "D4") (pin "A") (pinfunction "A_A") (pintype "passive"))
      (node (ref "E") (pin "1") (pinfunction "C_1") (pintype "passive"))
      (node (ref "E") (pin "2") (pinfunction "C_2") (pintype "passive"))
      (node (ref "F") (pin "1") (pinfunction "C_1") (pintype "passive"))
      (node (ref "F") (pin "2") (pinfunction "C_2") (pintype "passive"))
      (node (ref "G") (pin "1") (pinfunction "C_1") (pintype "passive"))
      (node (ref "G") (pin "2") (pinfunction "C_2") (pintype "passive"))
    )
    (net (code "30") (name "Net-(BKSP-C-Pad1)") (class "Default")
      (node (ref "BKSP") (pin "1") (pinfunction "C_1") (pintype "passive"))
      (node (ref "BKSP") (pin "2") (pinfunction "C_2") (pintype "passive"))
      (node (ref "D1") (pin "A") (pinfunction "A_A") (pintype "passive"))
      (node (ref "DOWN") (pin "1") (pinfunction "C_1") (pintype "passive"))
      (node (ref "DOWN") (pin "2") (pinfunction "C_2") (pintype "passive"))
      (node (ref "LEFT") (pin "1") (pinfunction "C_1") (pintype "passive"))
      (node (ref "LEFT") (pin "2") (pinfunction "C_2") (pintype "passive"))
      (node (ref "LF") (pin "1") (pinfunction "C_1") (pintype "passive"))
      (node (ref "LF") (pin "2") (pinfunction "C_2") (pintype "passive"))
      (node (ref "RETURN") (pin "1") (pinfunction "C_1") (pintype "passive"))
      (node (ref "RETURN") (pin "2") (pinfunction "C_2") (pintype "passive"))
      (node (ref "RIGHT") (pin "1") (pinfunction "C_1") (pintype "passive"))
      (node (ref "RIGHT") (pin "2") (pinfunction "C_2") (pintype "passive"))
      (node (ref "TAB") (pin "1") (pinfunction "C_1") (pintype "passive"))
      (node (ref "TAB") (pin "2") (pinfunction "C_2") (pintype "passive"))
      (node (ref "UP") (pin "1") (pinfunction "C_1") (pintype "passive"))
      (node (ref "UP") (pin "2") (pinfunction "C_2") (pintype "passive"))
    )
    (net (code "31") (name "Net-(CLR-C-Pad1)") (class "Default")
      (node (ref "CLR") (pin "1") (pinfunction "C_1") (pintype "passive"))
      (node (ref "CLR") (pin "2") (pinfunction "C_2") (pintype "passive"))
      (node (ref "D8") (pin "A") (pinfunction "A_A") (pintype "passive"))
      (node (ref "ESC") (pin "1") (pinfunction "C_1") (pintype "passive"))
      (node (ref "ESC") (pin "2") (pinfunction "C_2") (pintype "passive"))
      (node (ref "F1") (pin "1") (pinfunction "C_1") (pintype "passive"))
      (node (ref "F1") (pin "2") (pinfunction "C_2") (pintype "passive"))
      (node (ref "F2") (pin "1") (pinfunction "C_1") (pintype "passive"))
      (node (ref "F2") (pin "2") (pinfunction "C_2") (pintype "passive"))
      (node (ref "F3") (pin "1") (pinfunction "C_1") (pintype "passive"))
      (node (ref "F3") (pin "2") (pinfunction "C_2") (pintype "passive"))
      (node (ref "F4") (pin "1") (pinfunction "C_1") (pintype "passive"))
      (node (ref "F4") (pin "2") (pinfunction "C_2") (pintype "passive"))
      (node (ref "HOME") (pin "1") (pinfunction "C_1") (pintype "passive"))
      (node (ref "HOME") (pin "2") (pinfunction "C_2") (pintype "passive"))
    )
    (net (code "32") (name "Net-(D5-PadA)") (class "Default")
      (node (ref "D5") (pin "A") (pinfunction "A_A") (pintype "passive"))
      (node (ref "H") (pin "1") (pinfunction "C_1") (pintype "passive"))
      (node (ref "H") (pin "2") (pinfunction "C_2") (pintype "passive"))
      (node (ref "I") (pin "1") (pinfunction "C_1") (pintype "passive"))
      (node (ref "I") (pin "2") (pinfunction "C_2") (pintype "passive"))
      (node (ref "J") (pin "1") (pinfunction "C_1") (pintype "passive"))
      (node (ref "J") (pin "2") (pinfunction "C_2") (pintype "passive"))
      (node (ref "K") (pin "1") (pinfunction "C_1") (pintype "passive"))
      (node (ref "K") (pin "2") (pinfunction "C_2") (pintype "passive"))
      (node (ref "L") (pin "1") (pinfunction "C_1") (pintype "passive"))
      (node (ref "L") (pin "2") (pinfunction "C_2") (pintype "passive"))
      (node (ref "M") (pin "1") (pinfunction "C_1") (pintype "passive"))
      (node (ref "M") (pin "2") (pinfunction "C_2") (pintype "passive"))
      (node (ref "N") (pin "1") (pinfunction "C_1") (pintype "passive"))
      (node (ref "N") (pin "2") (pinfunction "C_2") (pintype "passive"))
      (node (ref "O") (pin "1") (pinfunction "C_1") (pintype "passive"))
      (node (ref "O") (pin "2") (pinfunction "C_2") (pintype "passive"))
    )
    (net (code "33") (name "Net-(D6-PadA)") (class "Default")
      (node (ref "D6") (pin "A") (pinfunction "A_A") (pintype "passive"))
      (node (ref "P") (pin "1") (pinfunction "C_1") (pintype "passive"))
      (node (ref "P") (pin "2") (pinfunction "C_2") (pintype "passive"))
      (node (ref "Q") (pin "1") (pinfunction "C_1") (pintype "passive"))
      (node (ref "Q") (pin "2") (pinfunction "C_2") (pintype "passive"))
      (node (ref "R") (pin "1") (pinfunction "C_1") (pintype "passive"))
      (node (ref "R") (pin "2") (pinfunction "C_2") (pintype "passive"))
      (node (ref "S") (pin "1") (pinfunction "C_1") (pintype "passive"))
      (node (ref "S") (pin "2") (pinfunction "C_2") (pintype "passive"))
      (node (ref "T") (pin "1") (pinfunction "C_1") (pintype "passive"))
      (node (ref "T") (pin "2") (pinfunction "C_2") (pintype "passive"))
      (node (ref "U") (pin "1") (pinfunction "C_1") (pintype "passive"))
      (node (ref "U") (pin "2") (pinfunction "C_2") (pintype "passive"))
      (node (ref "V") (pin "1") (pinfunction "C_1") (pintype "passive"))
      (node (ref "V") (pin "2") (pinfunction "C_2") (pintype "passive"))
      (node (ref "W") (pin "1") (pinfunction "C_1") (pintype "passive"))
      (node (ref "W") (pin "2") (pinfunction "C_2") (pintype "passive"))
    )
    (net (code "34") (name "Net-(D7-PadA)") (class "Default")
      (node (ref "D7") (pin "A") (pinfunction "A_A") (pintype "passive"))
      (node (ref "SPACE") (pin "1") (pinfunction "C_1") (pintype "passive"))
      (node (ref "SPACE") (pin "2") (pinfunction "C_2") (pintype "passive"))
      (node (ref "X") (pin "1") (pinfunction "C_1") (pintype "passive"))
      (node (ref "X") (pin "2") (pinfunction "C_2") (pintype "passive"))
      (node (ref "Y") (pin "1") (pinfunction "C_1") (pintype "passive"))
      (node (ref "Y") (pin "2") (pinfunction "C_2") (pintype "passive"))
      (node (ref "Z") (pin "1") (pinfunction "C_1") (pintype "passive"))
      (node (ref "Z") (pin "2") (pinfunction "C_2") (pintype "passive"))
      (node (ref "[") (pin "1") (pinfunction "C_1") (pintype "passive"))
      (node (ref "[") (pin "2") (pinfunction "C_2") (pintype "passive"))
      (node (ref "\\\\") (pin "1") (pinfunction "C_1") (pintype "passive"))
      (node (ref "\\\\") (pin "2") (pinfunction "C_2") (pintype "passive"))
      (node (ref "]") (pin "1") (pinfunction "C_1") (pintype "passive"))
      (node (ref "]") (pin "2") (pinfunction "C_2") (pintype "passive"))
      (node (ref "^") (pin "1") (pinfunction "C_1") (pintype "passive"))
      (node (ref "^") (pin "2") (pinfunction "C_2") (pintype "passive"))
    )
    (net (code "35") (name "Net-(R13-P$1)") (class "Default")
      (node (ref "R13") (pin "1") (pinfunction "P$1_1") (pintype "passive"))
      (node (ref "RUS") (pin "A") (pinfunction "A_A") (pintype "passive"))
    )
    (net (code "36") (name "Net-(R14-P$1)") (class "Default")
      (node (ref "PWR") (pin "A") (pinfunction "A_A") (pintype "passive"))
      (node (ref "R14") (pin "1") (pinfunction "P$1_1") (pintype "passive"))
    )
  )
)
